# CE842170260_SHEET5.net
KiCad netlist of a schematic drawn in Altium Designer
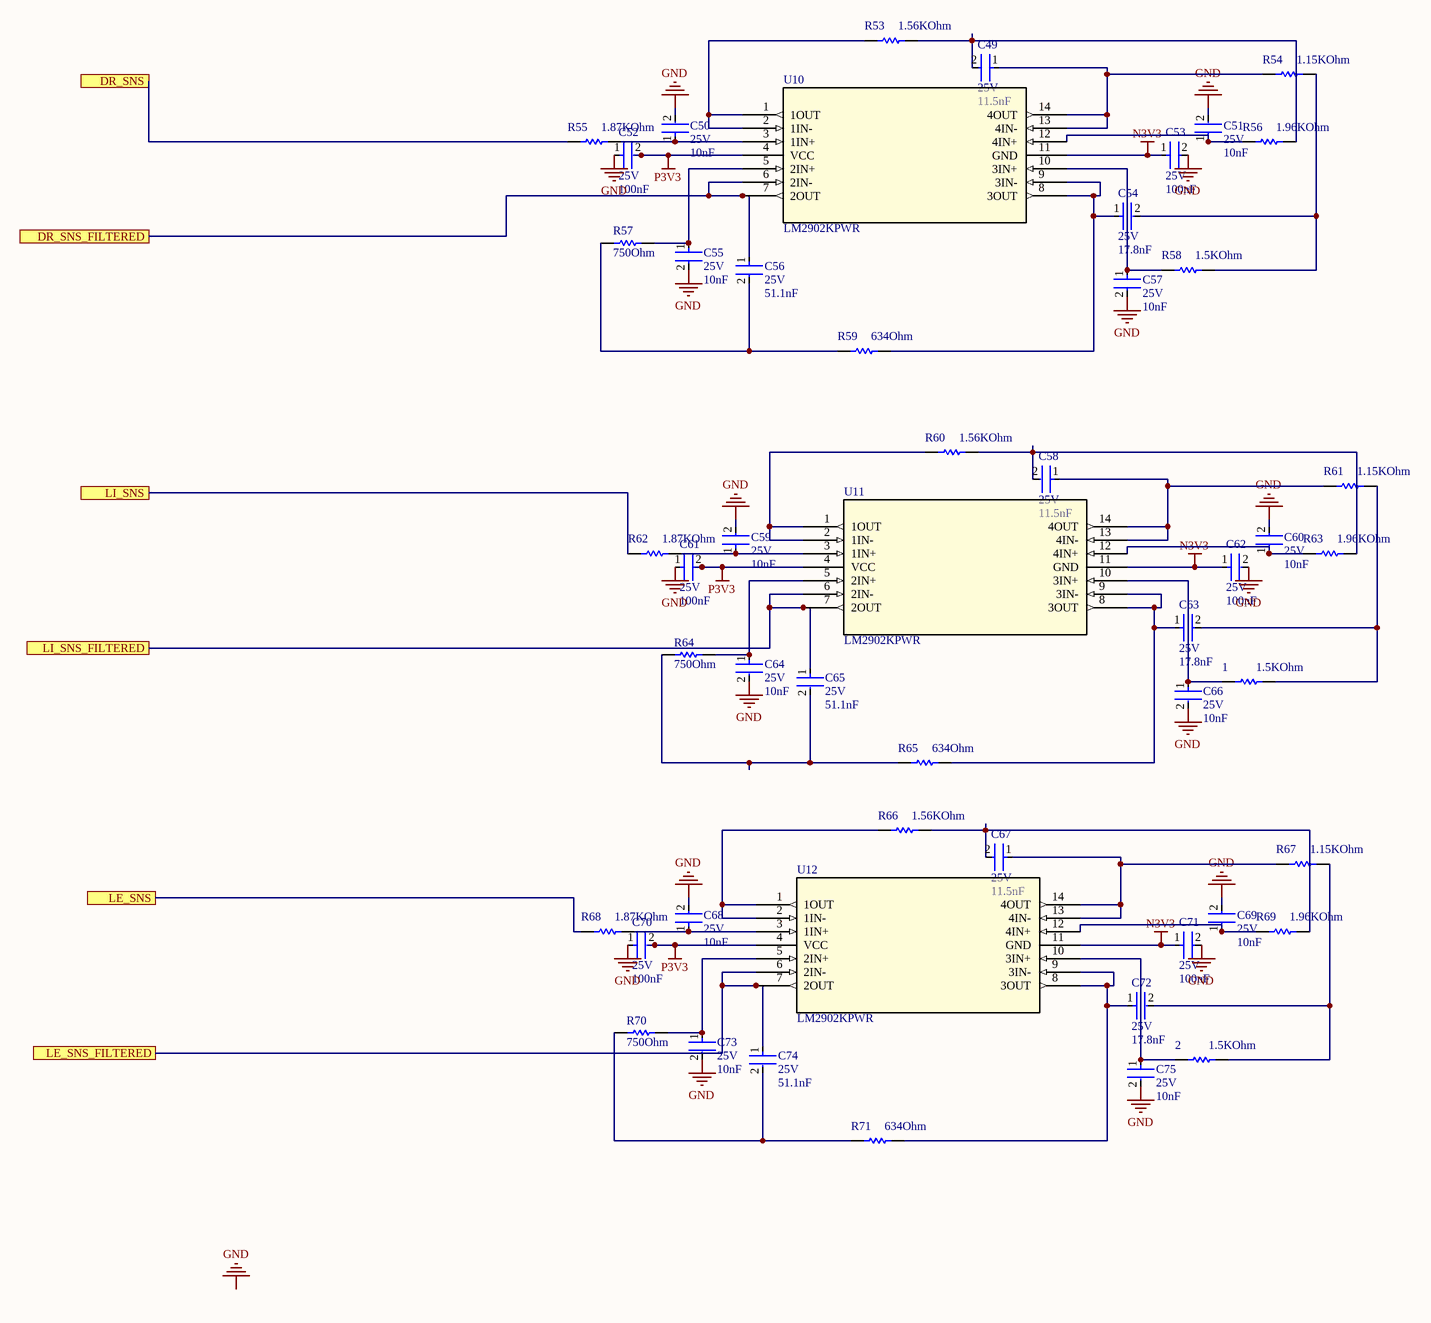
[diagram p0: CE842170260_SHEET5.SchDoc]

(export (version "E")
  (design (tool "Eeschema 10.0.6"))
  (components
    (comp (ref "1")
      (value "ERJ2RKF1002X")
      (footprint "RESC1005X40X25LL05T05")
      (description "Chip Resistor, 10 KOhm, +/- 1%, 0.1 W, -55 to 155 degC, 0402 (1005 Metric), RoHS, Tape and Reel")
      (fields
        (field (name "RESISTANCE") "1.5KOhm")
        (field (name "TOLERANCE") "1%")
        (field (name "MANUFACTURER") "Panasonic")
      )
      (libsource (lib "Altium Content Vault") (part "RES-2"))
    )
    (comp (ref "2")
      (value "ERJ2RKF1002X")
      (footprint "RESC1005X40X25LL05T05")
      (description "Chip Resistor, 10 KOhm, +/- 1%, 0.1 W, -55 to 155 degC, 0402 (1005 Metric), RoHS, Tape and Reel")
      (fields
        (field (name "RESISTANCE") "1.5KOhm")
        (field (name "TOLERANCE") "1%")
        (field (name "MANUFACTURER") "Panasonic")
      )
      (libsource (lib "Altium Content Vault") (part "RES-2"))
    )
    (comp (ref "C49")
      (value "C1005X5R1E104K050BC")
      (footprint "FP-C1005-050-0_05-MFG")
      (description "Multilayer Ceramic Capacitors 100nF ±10% 25V X5R SMD 0402")
      (fields
        (field (name "VOLTAGE RATING (DC)") "25V")
        (field (name "CAPACITANCE") "11.5nF")
        (field (name "TOLERANCE") "10%")
        (field (name "VOLTAGE") "25V")
      )
      (libsource (lib "Altium Content Vault") (part "b4654b650e69147ec39a6b967a45e02"))
    )
    (comp (ref "C50")
      (value "C1005X5R1E104K050BC")
      (footprint "FP-C1005-050-0_05-MFG")
      (description "Multilayer Ceramic Capacitors 100nF ±10% 25V X5R SMD 0402")
      (fields
        (field (name "VOLTAGE RATING (DC)") "25V")
        (field (name "CAPACITANCE") "10nF")
        (field (name "TOLERANCE") "10%")
        (field (name "VOLTAGE") "25V")
      )
      (libsource (lib "Altium Content Vault") (part "b4654b650e69147ec39a6b967a45e02"))
    )
    (comp (ref "C51")
      (value "C1005X5R1E104K050BC")
      (footprint "FP-C1005-050-0_05-MFG")
      (description "Multilayer Ceramic Capacitors 100nF ±10% 25V X5R SMD 0402")
      (fields
        (field (name "VOLTAGE RATING (DC)") "25V")
        (field (name "CAPACITANCE") "10nF")
        (field (name "TOLERANCE") "10%")
        (field (name "VOLTAGE") "25V")
      )
      (libsource (lib "Altium Content Vault") (part "b4654b650e69147ec39a6b967a45e02"))
    )
    (comp (ref "C52")
      (value "C1005X5R1E104K050BC")
      (footprint "FP-C1005-050-0_05-MFG")
      (description "Multilayer Ceramic Capacitors 100nF ±10% 25V X5R SMD 0402")
      (fields
        (field (name "VOLTAGE RATING (DC)") "25V")
        (field (name "CAPACITANCE") "100nF")
        (field (name "TOLERANCE") "10%")
        (field (name "VOLTAGE") "25V")
      )
      (libsource (lib "Altium Content Vault") (part "b4654b650e69147ec39a6b967a45e02"))
    )
    (comp (ref "C53")
      (value "C1005X5R1E104K050BC")
      (footprint "FP-C1005-050-0_05-MFG")
      (description "Multilayer Ceramic Capacitors 100nF ±10% 25V X5R SMD 0402")
      (fields
        (field (name "VOLTAGE RATING (DC)") "25V")
        (field (name "CAPACITANCE") "100nF")
        (field (name "TOLERANCE") "10%")
        (field (name "VOLTAGE") "25V")
      )
      (libsource (lib "Altium Content Vault") (part "b4654b650e69147ec39a6b967a45e02"))
    )
    (comp (ref "C54")
      (value "C1005X5R1E104K050BC")
      (footprint "FP-C1005-050-0_05-MFG")
      (description "Multilayer Ceramic Capacitors 100nF ±10% 25V X5R SMD 0402")
      (fields
        (field (name "VOLTAGE RATING (DC)") "25V")
        (field (name "CAPACITANCE") "17.8nF")
        (field (name "TOLERANCE") "10%")
        (field (name "VOLTAGE") "25V")
      )
      (libsource (lib "Altium Content Vault") (part "b4654b650e69147ec39a6b967a45e02"))
    )
    (comp (ref "C55")
      (value "C1005X5R1E104K050BC")
      (footprint "FP-C1005-050-0_05-MFG")
      (description "Multilayer Ceramic Capacitors 100nF ±10% 25V X5R SMD 0402")
      (fields
        (field (name "VOLTAGE RATING (DC)") "25V")
        (field (name "CAPACITANCE") "10nF")
        (field (name "TOLERANCE") "10%")
        (field (name "VOLTAGE") "25V")
      )
      (libsource (lib "Altium Content Vault") (part "b4654b650e69147ec39a6b967a45e02"))
    )
    (comp (ref "C56")
      (value "C1005X5R1E104K050BC")
      (footprint "FP-C1005-050-0_05-MFG")
      (description "Multilayer Ceramic Capacitors 100nF ±10% 25V X5R SMD 0402")
      (fields
        (field (name "VOLTAGE RATING (DC)") "25V")
        (field (name "CAPACITANCE") "51.1nF")
        (field (name "TOLERANCE") "10%")
        (field (name "VOLTAGE") "25V")
      )
      (libsource (lib "Altium Content Vault") (part "b4654b650e69147ec39a6b967a45e02"))
    )
    (comp (ref "C57")
      (value "C1005X5R1E104K050BC")
      (footprint "FP-C1005-050-0_05-MFG")
      (description "Multilayer Ceramic Capacitors 100nF ±10% 25V X5R SMD 0402")
      (fields
        (field (name "VOLTAGE RATING (DC)") "25V")
        (field (name "CAPACITANCE") "10nF")
        (field (name "TOLERANCE") "10%")
        (field (name "VOLTAGE") "25V")
      )
      (libsource (lib "Altium Content Vault") (part "b4654b650e69147ec39a6b967a45e02"))
    )
    (comp (ref "C58")
      (value "C1005X5R1E104K050BC")
      (footprint "FP-C1005-050-0_05-MFG")
      (description "Multilayer Ceramic Capacitors 100nF ±10% 25V X5R SMD 0402")
      (fields
        (field (name "VOLTAGE RATING (DC)") "25V")
        (field (name "CAPACITANCE") "11.5nF")
        (field (name "TOLERANCE") "10%")
        (field (name "VOLTAGE") "25V")
      )
      (libsource (lib "Altium Content Vault") (part "b4654b650e69147ec39a6b967a45e02"))
    )
    (comp (ref "C59")
      (value "C1005X5R1E104K050BC")
      (footprint "FP-C1005-050-0_05-MFG")
      (description "Multilayer Ceramic Capacitors 100nF ±10% 25V X5R SMD 0402")
      (fields
        (field (name "VOLTAGE RATING (DC)") "25V")
        (field (name "CAPACITANCE") "10nF")
        (field (name "TOLERANCE") "10%")
        (field (name "VOLTAGE") "25V")
      )
      (libsource (lib "Altium Content Vault") (part "b4654b650e69147ec39a6b967a45e02"))
    )
    (comp (ref "C60")
      (value "C1005X5R1E104K050BC")
      (footprint "FP-C1005-050-0_05-MFG")
      (description "Multilayer Ceramic Capacitors 100nF ±10% 25V X5R SMD 0402")
      (fields
        (field (name "VOLTAGE RATING (DC)") "25V")
        (field (name "CAPACITANCE") "10nF")
        (field (name "TOLERANCE") "10%")
        (field (name "VOLTAGE") "25V")
      )
      (libsource (lib "Altium Content Vault") (part "b4654b650e69147ec39a6b967a45e02"))
    )
    (comp (ref "C61")
      (value "C1005X5R1E104K050BC")
      (footprint "FP-C1005-050-0_05-MFG")
      (description "Multilayer Ceramic Capacitors 100nF ±10% 25V X5R SMD 0402")
      (fields
        (field (name "VOLTAGE RATING (DC)") "25V")
        (field (name "CAPACITANCE") "100nF")
        (field (name "TOLERANCE") "10%")
        (field (name "VOLTAGE") "25V")
      )
      (libsource (lib "Altium Content Vault") (part "b4654b650e69147ec39a6b967a45e02"))
    )
    (comp (ref "C62")
      (value "C1005X5R1E104K050BC")
      (footprint "FP-C1005-050-0_05-MFG")
      (description "Multilayer Ceramic Capacitors 100nF ±10% 25V X5R SMD 0402")
      (fields
        (field (name "VOLTAGE RATING (DC)") "25V")
        (field (name "CAPACITANCE") "100nF")
        (field (name "TOLERANCE") "10%")
        (field (name "VOLTAGE") "25V")
      )
      (libsource (lib "Altium Content Vault") (part "b4654b650e69147ec39a6b967a45e02"))
    )
    (comp (ref "C63")
      (value "C1005X5R1E104K050BC")
      (footprint "FP-C1005-050-0_05-MFG")
      (description "Multilayer Ceramic Capacitors 100nF ±10% 25V X5R SMD 0402")
      (fields
        (field (name "VOLTAGE RATING (DC)") "25V")
        (field (name "CAPACITANCE") "17.8nF")
        (field (name "TOLERANCE") "10%")
        (field (name "VOLTAGE") "25V")
      )
      (libsource (lib "Altium Content Vault") (part "b4654b650e69147ec39a6b967a45e02"))
    )
    (comp (ref "C64")
      (value "C1005X5R1E104K050BC")
      (footprint "FP-C1005-050-0_05-MFG")
      (description "Multilayer Ceramic Capacitors 100nF ±10% 25V X5R SMD 0402")
      (fields
        (field (name "VOLTAGE RATING (DC)") "25V")
        (field (name "CAPACITANCE") "10nF")
        (field (name "TOLERANCE") "10%")
        (field (name "VOLTAGE") "25V")
      )
      (libsource (lib "Altium Content Vault") (part "b4654b650e69147ec39a6b967a45e02"))
    )
    (comp (ref "C65")
      (value "C1005X5R1E104K050BC")
      (footprint "FP-C1005-050-0_05-MFG")
      (description "Multilayer Ceramic Capacitors 100nF ±10% 25V X5R SMD 0402")
      (fields
        (field (name "VOLTAGE RATING (DC)") "25V")
        (field (name "CAPACITANCE") "51.1nF")
        (field (name "TOLERANCE") "10%")
        (field (name "VOLTAGE") "25V")
      )
      (libsource (lib "Altium Content Vault") (part "b4654b650e69147ec39a6b967a45e02"))
    )
    (comp (ref "C66")
      (value "C1005X5R1E104K050BC")
      (footprint "FP-C1005-050-0_05-MFG")
      (description "Multilayer Ceramic Capacitors 100nF ±10% 25V X5R SMD 0402")
      (fields
        (field (name "VOLTAGE RATING (DC)") "25V")
        (field (name "CAPACITANCE") "10nF")
        (field (name "TOLERANCE") "10%")
        (field (name "VOLTAGE") "25V")
      )
      (libsource (lib "Altium Content Vault") (part "b4654b650e69147ec39a6b967a45e02"))
    )
    (comp (ref "C67")
      (value "C1005X5R1E104K050BC")
      (footprint "FP-C1005-050-0_05-MFG")
      (description "Multilayer Ceramic Capacitors 100nF ±10% 25V X5R SMD 0402")
      (fields
        (field (name "VOLTAGE RATING (DC)") "25V")
        (field (name "CAPACITANCE") "11.5nF")
        (field (name "TOLERANCE") "10%")
        (field (name "VOLTAGE") "25V")
      )
      (libsource (lib "Altium Content Vault") (part "b4654b650e69147ec39a6b967a45e02"))
    )
    (comp (ref "C68")
      (value "C1005X5R1E104K050BC")
      (footprint "FP-C1005-050-0_05-MFG")
      (description "Multilayer Ceramic Capacitors 100nF ±10% 25V X5R SMD 0402")
      (fields
        (field (name "VOLTAGE RATING (DC)") "25V")
        (field (name "CAPACITANCE") "10nF")
        (field (name "TOLERANCE") "10%")
        (field (name "VOLTAGE") "25V")
      )
      (libsource (lib "Altium Content Vault") (part "b4654b650e69147ec39a6b967a45e02"))
    )
    (comp (ref "C69")
      (value "C1005X5R1E104K050BC")
      (footprint "FP-C1005-050-0_05-MFG")
      (description "Multilayer Ceramic Capacitors 100nF ±10% 25V X5R SMD 0402")
      (fields
        (field (name "VOLTAGE RATING (DC)") "25V")
        (field (name "CAPACITANCE") "10nF")
        (field (name "TOLERANCE") "10%")
        (field (name "VOLTAGE") "25V")
      )
      (libsource (lib "Altium Content Vault") (part "b4654b650e69147ec39a6b967a45e02"))
    )
    (comp (ref "C70")
      (value "C1005X5R1E104K050BC")
      (footprint "FP-C1005-050-0_05-MFG")
      (description "Multilayer Ceramic Capacitors 100nF ±10% 25V X5R SMD 0402")
      (fields
        (field (name "VOLTAGE RATING (DC)") "25V")
        (field (name "CAPACITANCE") "100nF")
        (field (name "TOLERANCE") "10%")
        (field (name "VOLTAGE") "25V")
      )
      (libsource (lib "Altium Content Vault") (part "b4654b650e69147ec39a6b967a45e02"))
    )
    (comp (ref "C71")
      (value "C1005X5R1E104K050BC")
      (footprint "FP-C1005-050-0_05-MFG")
      (description "Multilayer Ceramic Capacitors 100nF ±10% 25V X5R SMD 0402")
      (fields
        (field (name "VOLTAGE RATING (DC)") "25V")
        (field (name "CAPACITANCE") "100nF")
        (field (name "TOLERANCE") "10%")
        (field (name "VOLTAGE") "25V")
      )
      (libsource (lib "Altium Content Vault") (part "b4654b650e69147ec39a6b967a45e02"))
    )
    (comp (ref "C72")
      (value "C1005X5R1E104K050BC")
      (footprint "FP-C1005-050-0_05-MFG")
      (description "Multilayer Ceramic Capacitors 100nF ±10% 25V X5R SMD 0402")
      (fields
        (field (name "VOLTAGE RATING (DC)") "25V")
        (field (name "CAPACITANCE") "17.8nF")
        (field (name "TOLERANCE") "10%")
        (field (name "VOLTAGE") "25V")
      )
      (libsource (lib "Altium Content Vault") (part "b4654b650e69147ec39a6b967a45e02"))
    )
    (comp (ref "C73")
      (value "C1005X5R1E104K050BC")
      (footprint "FP-C1005-050-0_05-MFG")
      (description "Multilayer Ceramic Capacitors 100nF ±10% 25V X5R SMD 0402")
      (fields
        (field (name "VOLTAGE RATING (DC)") "25V")
        (field (name "CAPACITANCE") "10nF")
        (field (name "TOLERANCE") "10%")
        (field (name "VOLTAGE") "25V")
      )
      (libsource (lib "Altium Content Vault") (part "b4654b650e69147ec39a6b967a45e02"))
    )
    (comp (ref "C74")
      (value "C1005X5R1E104K050BC")
      (footprint "FP-C1005-050-0_05-MFG")
      (description "Multilayer Ceramic Capacitors 100nF ±10% 25V X5R SMD 0402")
      (fields
        (field (name "VOLTAGE RATING (DC)") "25V")
        (field (name "CAPACITANCE") "51.1nF")
        (field (name "TOLERANCE") "10%")
        (field (name "VOLTAGE") "25V")
      )
      (libsource (lib "Altium Content Vault") (part "b4654b650e69147ec39a6b967a45e02"))
    )
    (comp (ref "C75")
      (value "C1005X5R1E104K050BC")
      (footprint "FP-C1005-050-0_05-MFG")
      (description "Multilayer Ceramic Capacitors 100nF ±10% 25V X5R SMD 0402")
      (fields
        (field (name "VOLTAGE RATING (DC)") "25V")
        (field (name "CAPACITANCE") "10nF")
        (field (name "TOLERANCE") "10%")
        (field (name "VOLTAGE") "25V")
      )
      (libsource (lib "Altium Content Vault") (part "b4654b650e69147ec39a6b967a45e02"))
    )
    (comp (ref "R53")
      (value "ERJ2RKF1002X")
      (footprint "RESC1005X40X25LL05T05")
      (description "Chip Resistor, 10 KOhm, +/- 1%, 0.1 W, -55 to 155 degC, 0402 (1005 Metric), RoHS, Tape and Reel")
      (fields
        (field (name "RESISTANCE") "1.56KOhm")
        (field (name "TOLERANCE") "1%")
        (field (name "MANUFACTURER") "Panasonic")
      )
      (libsource (lib "Altium Content Vault") (part "RES-2"))
    )
    (comp (ref "R54")
      (value "ERJ2RKF1002X")
      (footprint "RESC1005X40X25LL05T05")
      (description "Chip Resistor, 10 KOhm, +/- 1%, 0.1 W, -55 to 155 degC, 0402 (1005 Metric), RoHS, Tape and Reel")
      (fields
        (field (name "RESISTANCE") "1.15KOhm")
        (field (name "TOLERANCE") "1%")
        (field (name "MANUFACTURER") "Panasonic")
      )
      (libsource (lib "Altium Content Vault") (part "RES-2"))
    )
    (comp (ref "R55")
      (value "ERJ2RKF1002X")
      (footprint "RESC1005X40X25LL05T05")
      (description "Chip Resistor, 10 KOhm, +/- 1%, 0.1 W, -55 to 155 degC, 0402 (1005 Metric), RoHS, Tape and Reel")
      (fields
        (field (name "RESISTANCE") "1.87KOhm")
        (field (name "TOLERANCE") "1%")
        (field (name "MANUFACTURER") "Panasonic")
      )
      (libsource (lib "Altium Content Vault") (part "RES-2"))
    )
    (comp (ref "R56")
      (value "ERJ2RKF1002X")
      (footprint "RESC1005X40X25LL05T05")
      (description "Chip Resistor, 10 KOhm, +/- 1%, 0.1 W, -55 to 155 degC, 0402 (1005 Metric), RoHS, Tape and Reel")
      (fields
        (field (name "RESISTANCE") "1.96KOhm")
        (field (name "TOLERANCE") "1%")
        (field (name "MANUFACTURER") "Panasonic")
      )
      (libsource (lib "Altium Content Vault") (part "RES-2"))
    )
    (comp (ref "R57")
      (value "ERJ2RKF1002X")
      (footprint "RESC1005X40X25LL05T05")
      (description "Chip Resistor, 10 KOhm, +/- 1%, 0.1 W, -55 to 155 degC, 0402 (1005 Metric), RoHS, Tape and Reel")
      (fields
        (field (name "RESISTANCE") "750Ohm")
        (field (name "TOLERANCE") "1%")
        (field (name "MANUFACTURER") "Panasonic")
      )
      (libsource (lib "Altium Content Vault") (part "RES-2"))
    )
    (comp (ref "R58")
      (value "ERJ2RKF1002X")
      (footprint "RESC1005X40X25LL05T05")
      (description "Chip Resistor, 10 KOhm, +/- 1%, 0.1 W, -55 to 155 degC, 0402 (1005 Metric), RoHS, Tape and Reel")
      (fields
        (field (name "RESISTANCE") "1.5KOhm")
        (field (name "TOLERANCE") "1%")
        (field (name "MANUFACTURER") "Panasonic")
      )
      (libsource (lib "Altium Content Vault") (part "RES-2"))
    )
    (comp (ref "R59")
      (value "ERJ2RKF1002X")
      (footprint "RESC1005X40X25LL05T05")
      (description "Chip Resistor, 10 KOhm, +/- 1%, 0.1 W, -55 to 155 degC, 0402 (1005 Metric), RoHS, Tape and Reel")
      (fields
        (field (name "RESISTANCE") "634Ohm")
        (field (name "TOLERANCE") "1%")
        (field (name "MANUFACTURER") "Panasonic")
      )
      (libsource (lib "Altium Content Vault") (part "RES-2"))
    )
    (comp (ref "R60")
      (value "ERJ2RKF1002X")
      (footprint "RESC1005X40X25LL05T05")
      (description "Chip Resistor, 10 KOhm, +/- 1%, 0.1 W, -55 to 155 degC, 0402 (1005 Metric), RoHS, Tape and Reel")
      (fields
        (field (name "RESISTANCE") "1.56KOhm")
        (field (name "TOLERANCE") "1%")
        (field (name "MANUFACTURER") "Panasonic")
      )
      (libsource (lib "Altium Content Vault") (part "RES-2"))
    )
    (comp (ref "R61")
      (value "ERJ2RKF1002X")
      (footprint "RESC1005X40X25LL05T05")
      (description "Chip Resistor, 10 KOhm, +/- 1%, 0.1 W, -55 to 155 degC, 0402 (1005 Metric), RoHS, Tape and Reel")
      (fields
        (field (name "RESISTANCE") "1.15KOhm")
        (field (name "TOLERANCE") "1%")
        (field (name "MANUFACTURER") "Panasonic")
      )
      (libsource (lib "Altium Content Vault") (part "RES-2"))
    )
    (comp (ref "R62")
      (value "ERJ2RKF1002X")
      (footprint "RESC1005X40X25LL05T05")
      (description "Chip Resistor, 10 KOhm, +/- 1%, 0.1 W, -55 to 155 degC, 0402 (1005 Metric), RoHS, Tape and Reel")
      (fields
        (field (name "RESISTANCE") "1.87KOhm")
        (field (name "TOLERANCE") "1%")
        (field (name "MANUFACTURER") "Panasonic")
      )
      (libsource (lib "Altium Content Vault") (part "RES-2"))
    )
    (comp (ref "R63")
      (value "ERJ2RKF1002X")
      (footprint "RESC1005X40X25LL05T05")
      (description "Chip Resistor, 10 KOhm, +/- 1%, 0.1 W, -55 to 155 degC, 0402 (1005 Metric), RoHS, Tape and Reel")
      (fields
        (field (name "RESISTANCE") "1.96KOhm")
        (field (name "TOLERANCE") "1%")
        (field (name "MANUFACTURER") "Panasonic")
      )
      (libsource (lib "Altium Content Vault") (part "RES-2"))
    )
    (comp (ref "R64")
      (value "ERJ2RKF1002X")
      (footprint "RESC1005X40X25LL05T05")
      (description "Chip Resistor, 10 KOhm, +/- 1%, 0.1 W, -55 to 155 degC, 0402 (1005 Metric), RoHS, Tape and Reel")
      (fields
        (field (name "RESISTANCE") "750Ohm")
        (field (name "TOLERANCE") "1%")
        (field (name "MANUFACTURER") "Panasonic")
      )
      (libsource (lib "Altium Content Vault") (part "RES-2"))
    )
    (comp (ref "R65")
      (value "ERJ2RKF1002X")
      (footprint "RESC1005X40X25LL05T05")
      (description "Chip Resistor, 10 KOhm, +/- 1%, 0.1 W, -55 to 155 degC, 0402 (1005 Metric), RoHS, Tape and Reel")
      (fields
        (field (name "RESISTANCE") "634Ohm")
        (field (name "TOLERANCE") "1%")
        (field (name "MANUFACTURER") "Panasonic")
      )
      (libsource (lib "Altium Content Vault") (part "RES-2"))
    )
    (comp (ref "R66")
      (value "ERJ2RKF1002X")
      (footprint "RESC1005X40X25LL05T05")
      (description "Chip Resistor, 10 KOhm, +/- 1%, 0.1 W, -55 to 155 degC, 0402 (1005 Metric), RoHS, Tape and Reel")
      (fields
        (field (name "RESISTANCE") "1.56KOhm")
        (field (name "TOLERANCE") "1%")
        (field (name "MANUFACTURER") "Panasonic")
      )
      (libsource (lib "Altium Content Vault") (part "RES-2"))
    )
    (comp (ref "R67")
      (value "ERJ2RKF1002X")
      (footprint "RESC1005X40X25LL05T05")
      (description "Chip Resistor, 10 KOhm, +/- 1%, 0.1 W, -55 to 155 degC, 0402 (1005 Metric), RoHS, Tape and Reel")
      (fields
        (field (name "RESISTANCE") "1.15KOhm")
        (field (name "TOLERANCE") "1%")
        (field (name "MANUFACTURER") "Panasonic")
      )
      (libsource (lib "Altium Content Vault") (part "RES-2"))
    )
    (comp (ref "R68")
      (value "ERJ2RKF1002X")
      (footprint "RESC1005X40X25LL05T05")
      (description "Chip Resistor, 10 KOhm, +/- 1%, 0.1 W, -55 to 155 degC, 0402 (1005 Metric), RoHS, Tape and Reel")
      (fields
        (field (name "RESISTANCE") "1.87KOhm")
        (field (name "TOLERANCE") "1%")
        (field (name "MANUFACTURER") "Panasonic")
      )
      (libsource (lib "Altium Content Vault") (part "RES-2"))
    )
    (comp (ref "R69")
      (value "ERJ2RKF1002X")
      (footprint "RESC1005X40X25LL05T05")
      (description "Chip Resistor, 10 KOhm, +/- 1%, 0.1 W, -55 to 155 degC, 0402 (1005 Metric), RoHS, Tape and Reel")
      (fields
        (field (name "RESISTANCE") "1.96KOhm")
        (field (name "TOLERANCE") "1%")
        (field (name "MANUFACTURER") "Panasonic")
      )
      (libsource (lib "Altium Content Vault") (part "RES-2"))
    )
    (comp (ref "R70")
      (value "ERJ2RKF1002X")
      (footprint "RESC1005X40X25LL05T05")
      (description "Chip Resistor, 10 KOhm, +/- 1%, 0.1 W, -55 to 155 degC, 0402 (1005 Metric), RoHS, Tape and Reel")
      (fields
        (field (name "RESISTANCE") "750Ohm")
        (field (name "TOLERANCE") "1%")
        (field (name "MANUFACTURER") "Panasonic")
      )
      (libsource (lib "Altium Content Vault") (part "RES-2"))
    )
    (comp (ref "R71")
      (value "ERJ2RKF1002X")
      (footprint "RESC1005X40X25LL05T05")
      (description "Chip Resistor, 10 KOhm, +/- 1%, 0.1 W, -55 to 155 degC, 0402 (1005 Metric), RoHS, Tape and Reel")
      (fields
        (field (name "RESISTANCE") "634Ohm")
        (field (name "TOLERANCE") "1%")
        (field (name "MANUFACTURER") "Panasonic")
      )
      (libsource (lib "Altium Content Vault") (part "RES-2"))
    )
    (comp (ref "U10")
      (value "LM2902KPWR")
      (footprint "PW14")
      (description "No Description Available")
      (fields (field (name "COPYRIGHT") "Copyright (C) 2023 Ultra Librarian. All rights reserved."))
      (libsource (lib "LM2902KPWR") (part "LM2902KPWR"))
    )
    (comp (ref "U11")
      (value "LM2902KPWR")
      (footprint "PW14")
      (description "No Description Available")
      (fields (field (name "COPYRIGHT") "Copyright (C) 2023 Ultra Librarian. All rights reserved."))
      (libsource (lib "LM2902KPWR") (part "LM2902KPWR"))
    )
    (comp (ref "U12")
      (value "LM2902KPWR")
      (footprint "PW14")
      (description "No Description Available")
      (fields (field (name "COPYRIGHT") "Copyright (C) 2023 Ultra Librarian. All rights reserved."))
      (libsource (lib "LM2902KPWR") (part "LM2902KPWR"))
    )
  )
  (nets
    (net (code "1") (name "/DR_SNS") (class "Default")
      (node (ref "R55") (pin "1") (pinfunction "1_1") (pintype "passive"))
    )
    (net (code "2") (name "/DR_SNS_FILTERED") (class "Default")
      (node (ref "C56") (pin "1") (pinfunction "1_1") (pintype "passive"))
      (node (ref "U10") (pin "6") (pinfunction "2IN-_6") (pintype "input"))
      (node (ref "U10") (pin "7") (pinfunction "2OUT_7") (pintype "output"))
    )
    (net (code "3") (name "/LE_SNS") (class "Default")
      (node (ref "R68") (pin "1") (pinfunction "1_1") (pintype "passive"))
    )
    (net (code "4") (name "/LE_SNS_FILTERED") (class "Default")
      (node (ref "C74") (pin "1") (pinfunction "1_1") (pintype "passive"))
      (node (ref "U12") (pin "6") (pinfunction "2IN-_6") (pintype "input"))
      (node (ref "U12") (pin "7") (pinfunction "2OUT_7") (pintype "output"))
    )
    (net (code "5") (name "/LI_SNS") (class "Default")
      (node (ref "R62") (pin "1") (pinfunction "1_1") (pintype "passive"))
    )
    (net (code "6") (name "/LI_SNS_FILTERED") (class "Default")
      (node (ref "C65") (pin "1") (pinfunction "1_1") (pintype "passive"))
      (node (ref "U11") (pin "6") (pinfunction "2IN-_6") (pintype "input"))
      (node (ref "U11") (pin "7") (pinfunction "2OUT_7") (pintype "output"))
    )
    (net (code "7") (name "GND") (class "Default")
      (node (ref "C50") (pin "2") (pinfunction "2_2") (pintype "passive"))
      (node (ref "C51") (pin "2") (pinfunction "2_2") (pintype "passive"))
      (node (ref "C52") (pin "1") (pinfunction "1_1") (pintype "passive"))
      (node (ref "C53") (pin "2") (pinfunction "2_2") (pintype "passive"))
      (node (ref "C55") (pin "2") (pinfunction "2_2") (pintype "passive"))
      (node (ref "C57") (pin "2") (pinfunction "2_2") (pintype "passive"))
      (node (ref "C59") (pin "2") (pinfunction "2_2") (pintype "passive"))
      (node (ref "C60") (pin "2") (pinfunction "2_2") (pintype "passive"))
      (node (ref "C61") (pin "1") (pinfunction "1_1") (pintype "passive"))
      (node (ref "C62") (pin "2") (pinfunction "2_2") (pintype "passive"))
      (node (ref "C64") (pin "2") (pinfunction "2_2") (pintype "passive"))
      (node (ref "C66") (pin "2") (pinfunction "2_2") (pintype "passive"))
      (node (ref "C68") (pin "2") (pinfunction "2_2") (pintype "passive"))
      (node (ref "C69") (pin "2") (pinfunction "2_2") (pintype "passive"))
      (node (ref "C70") (pin "1") (pinfunction "1_1") (pintype "passive"))
      (node (ref "C71") (pin "2") (pinfunction "2_2") (pintype "passive"))
      (node (ref "C73") (pin "2") (pinfunction "2_2") (pintype "passive"))
      (node (ref "C75") (pin "2") (pinfunction "2_2") (pintype "passive"))
    )
    (net (code "8") (name "N3V3") (class "Default")
      (node (ref "C53") (pin "1") (pinfunction "1_1") (pintype "passive"))
      (node (ref "C62") (pin "1") (pinfunction "1_1") (pintype "passive"))
      (node (ref "C71") (pin "1") (pinfunction "1_1") (pintype "passive"))
      (node (ref "U10") (pin "11") (pinfunction "GND_11") (pintype "power_in"))
      (node (ref "U11") (pin "11") (pinfunction "GND_11") (pintype "power_in"))
      (node (ref "U12") (pin "11") (pinfunction "GND_11") (pintype "power_in"))
    )
    (net (code "9") (name "Net-(1-Pad2)") (class "Default")
      (node (ref "1") (pin "2") (pinfunction "2_2") (pintype "passive"))
      (node (ref "C63") (pin "2") (pinfunction "2_2") (pintype "passive"))
      (node (ref "R61") (pin "2") (pinfunction "2_2") (pintype "passive"))
    )
    (net (code "10") (name "Net-(2-Pad2)") (class "Default")
      (node (ref "2") (pin "2") (pinfunction "2_2") (pintype "passive"))
      (node (ref "C72") (pin "2") (pinfunction "2_2") (pintype "passive"))
      (node (ref "R67") (pin "2") (pinfunction "2_2") (pintype "passive"))
    )
    (net (code "11") (name "Net-(C49-Pad2)") (class "Default")
      (node (ref "C49") (pin "2") (pinfunction "2_2") (pintype "passive"))
      (node (ref "R53") (pin "2") (pinfunction "2_2") (pintype "passive"))
      (node (ref "R56") (pin "2") (pinfunction "2_2") (pintype "passive"))
    )
    (net (code "12") (name "Net-(C54-Pad2)") (class "Default")
      (node (ref "C54") (pin "2") (pinfunction "2_2") (pintype "passive"))
      (node (ref "R54") (pin "2") (pinfunction "2_2") (pintype "passive"))
      (node (ref "R58") (pin "2") (pinfunction "2_2") (pintype "passive"))
    )
    (net (code "13") (name "Net-(C56-Pad2)") (class "Default")
      (node (ref "C56") (pin "2") (pinfunction "2_2") (pintype "passive"))
      (node (ref "R57") (pin "2") (pinfunction "2_2") (pintype "passive"))
      (node (ref "R59") (pin "1") (pinfunction "1_1") (pintype "passive"))
    )
    (net (code "14") (name "Net-(C58-Pad2)") (class "Default")
      (node (ref "C58") (pin "2") (pinfunction "2_2") (pintype "passive"))
      (node (ref "R60") (pin "2") (pinfunction "2_2") (pintype "passive"))
      (node (ref "R63") (pin "2") (pinfunction "2_2") (pintype "passive"))
    )
    (net (code "15") (name "Net-(C65-Pad2)") (class "Default")
      (node (ref "C65") (pin "2") (pinfunction "2_2") (pintype "passive"))
      (node (ref "R64") (pin "2") (pinfunction "2_2") (pintype "passive"))
      (node (ref "R65") (pin "1") (pinfunction "1_1") (pintype "passive"))
    )
    (net (code "16") (name "Net-(C67-Pad2)") (class "Default")
      (node (ref "C67") (pin "2") (pinfunction "2_2") (pintype "passive"))
      (node (ref "R66") (pin "2") (pinfunction "2_2") (pintype "passive"))
      (node (ref "R69") (pin "2") (pinfunction "2_2") (pintype "passive"))
    )
    (net (code "17") (name "Net-(C74-Pad2)") (class "Default")
      (node (ref "C74") (pin "2") (pinfunction "2_2") (pintype "passive"))
      (node (ref "R70") (pin "2") (pinfunction "2_2") (pintype "passive"))
      (node (ref "R71") (pin "1") (pinfunction "1_1") (pintype "passive"))
    )
    (net (code "18") (name "Net-(U10-1IN+)") (class "Default")
      (node (ref "C50") (pin "1") (pinfunction "1_1") (pintype "passive"))
      (node (ref "R55") (pin "2") (pinfunction "2_2") (pintype "passive"))
      (node (ref "U10") (pin "3") (pinfunction "1IN+_3") (pintype "input"))
    )
    (net (code "19") (name "Net-(U10-1IN-)") (class "Default")
      (node (ref "R53") (pin "1") (pinfunction "1_1") (pintype "passive"))
      (node (ref "U10") (pin "1") (pinfunction "1OUT_1") (pintype "output"))
      (node (ref "U10") (pin "2") (pinfunction "1IN-_2") (pintype "input"))
    )
    (net (code "20") (name "Net-(U10-2IN+)") (class "Default")
      (node (ref "C55") (pin "1") (pinfunction "1_1") (pintype "passive"))
      (node (ref "R57") (pin "1") (pinfunction "1_1") (pintype "passive"))
      (node (ref "U10") (pin "5") (pinfunction "2IN+_5") (pintype "input"))
    )
    (net (code "21") (name "Net-(U10-3IN+)") (class "Default")
      (node (ref "C57") (pin "1") (pinfunction "1_1") (pintype "passive"))
      (node (ref "R58") (pin "1") (pinfunction "1_1") (pintype "passive"))
      (node (ref "U10") (pin "10") (pinfunction "3IN+_10") (pintype "input"))
    )
    (net (code "22") (name "Net-(U10-3IN-)") (class "Default")
      (node (ref "C54") (pin "1") (pinfunction "1_1") (pintype "passive"))
      (node (ref "R59") (pin "2") (pinfunction "2_2") (pintype "passive"))
      (node (ref "U10") (pin "8") (pinfunction "3OUT_8") (pintype "output"))
      (node (ref "U10") (pin "9") (pinfunction "3IN-_9") (pintype "input"))
    )
    (net (code "23") (name "Net-(U10-4IN+)") (class "Default")
      (node (ref "C51") (pin "1") (pinfunction "1_1") (pintype "passive"))
      (node (ref "R56") (pin "1") (pinfunction "1_1") (pintype "passive"))
      (node (ref "U10") (pin "12") (pinfunction "4IN+_12") (pintype "input"))
    )
    (net (code "24") (name "Net-(U10-4IN-)") (class "Default")
      (node (ref "C49") (pin "1") (pinfunction "1_1") (pintype "passive"))
      (node (ref "R54") (pin "1") (pinfunction "1_1") (pintype "passive"))
      (node (ref "U10") (pin "13") (pinfunction "4IN-_13") (pintype "input"))
      (node (ref "U10") (pin "14") (pinfunction "4OUT_14") (pintype "output"))
    )
    (net (code "25") (name "Net-(U11-1IN+)") (class "Default")
      (node (ref "C59") (pin "1") (pinfunction "1_1") (pintype "passive"))
      (node (ref "R62") (pin "2") (pinfunction "2_2") (pintype "passive"))
      (node (ref "U11") (pin "3") (pinfunction "1IN+_3") (pintype "input"))
    )
    (net (code "26") (name "Net-(U11-1IN-)") (class "Default")
      (node (ref "R60") (pin "1") (pinfunction "1_1") (pintype "passive"))
      (node (ref "U11") (pin "1") (pinfunction "1OUT_1") (pintype "output"))
      (node (ref "U11") (pin "2") (pinfunction "1IN-_2") (pintype "input"))
    )
    (net (code "27") (name "Net-(U11-2IN+)") (class "Default")
      (node (ref "C64") (pin "1") (pinfunction "1_1") (pintype "passive"))
      (node (ref "R64") (pin "1") (pinfunction "1_1") (pintype "passive"))
      (node (ref "U11") (pin "5") (pinfunction "2IN+_5") (pintype "input"))
    )
    (net (code "28") (name "Net-(U11-3IN+)") (class "Default")
      (node (ref "1") (pin "1") (pinfunction "1_1") (pintype "passive"))
      (node (ref "C66") (pin "1") (pinfunction "1_1") (pintype "passive"))
      (node (ref "U11") (pin "10") (pinfunction "3IN+_10") (pintype "input"))
    )
    (net (code "29") (name "Net-(U11-3IN-)") (class "Default")
      (node (ref "C63") (pin "1") (pinfunction "1_1") (pintype "passive"))
      (node (ref "R65") (pin "2") (pinfunction "2_2") (pintype "passive"))
      (node (ref "U11") (pin "8") (pinfunction "3OUT_8") (pintype "output"))
      (node (ref "U11") (pin "9") (pinfunction "3IN-_9") (pintype "input"))
    )
    (net (code "30") (name "Net-(U11-4IN+)") (class "Default")
      (node (ref "C60") (pin "1") (pinfunction "1_1") (pintype "passive"))
      (node (ref "R63") (pin "1") (pinfunction "1_1") (pintype "passive"))
      (node (ref "U11") (pin "12") (pinfunction "4IN+_12") (pintype "input"))
    )
    (net (code "31") (name "Net-(U11-4IN-)") (class "Default")
      (node (ref "C58") (pin "1") (pinfunction "1_1") (pintype "passive"))
      (node (ref "R61") (pin "1") (pinfunction "1_1") (pintype "passive"))
      (node (ref "U11") (pin "13") (pinfunction "4IN-_13") (pintype "input"))
      (node (ref "U11") (pin "14") (pinfunction "4OUT_14") (pintype "output"))
    )
    (net (code "32") (name "Net-(U12-1IN+)") (class "Default")
      (node (ref "C68") (pin "1") (pinfunction "1_1") (pintype "passive"))
      (node (ref "R68") (pin "2") (pinfunction "2_2") (pintype "passive"))
      (node (ref "U12") (pin "3") (pinfunction "1IN+_3") (pintype "input"))
    )
    (net (code "33") (name "Net-(U12-1IN-)") (class "Default")
      (node (ref "R66") (pin "1") (pinfunction "1_1") (pintype "passive"))
      (node (ref "U12") (pin "1") (pinfunction "1OUT_1") (pintype "output"))
      (node (ref "U12") (pin "2") (pinfunction "1IN-_2") (pintype "input"))
    )
    (net (code "34") (name "Net-(U12-2IN+)") (class "Default")
      (node (ref "C73") (pin "1") (pinfunction "1_1") (pintype "passive"))
      (node (ref "R70") (pin "1") (pinfunction "1_1") (pintype "passive"))
      (node (ref "U12") (pin "5") (pinfunction "2IN+_5") (pintype "input"))
    )
    (net (code "35") (name "Net-(U12-3IN+)") (class "Default")
      (node (ref "2") (pin "1") (pinfunction "1_1") (pintype "passive"))
      (node (ref "C75") (pin "1") (pinfunction "1_1") (pintype "passive"))
      (node (ref "U12") (pin "10") (pinfunction "3IN+_10") (pintype "input"))
    )
    (net (code "36") (name "Net-(U12-3IN-)") (class "Default")
      (node (ref "C72") (pin "1") (pinfunction "1_1") (pintype "passive"))
      (node (ref "R71") (pin "2") (pinfunction "2_2") (pintype "passive"))
      (node (ref "U12") (pin "8") (pinfunction "3OUT_8") (pintype "output"))
      (node (ref "U12") (pin "9") (pinfunction "3IN-_9") (pintype "input"))
    )
    (net (code "37") (name "Net-(U12-4IN+)") (class "Default")
      (node (ref "C69") (pin "1") (pinfunction "1_1") (pintype "passive"))
      (node (ref "R69") (pin "1") (pinfunction "1_1") (pintype "passive"))
      (node (ref "U12") (pin "12") (pinfunction "4IN+_12") (pintype "input"))
    )
    (net (code "38") (name "Net-(U12-4IN-)") (class "Default")
      (node (ref "C67") (pin "1") (pinfunction "1_1") (pintype "passive"))
      (node (ref "R67") (pin "1") (pinfunction "1_1") (pintype "passive"))
      (node (ref "U12") (pin "13") (pinfunction "4IN-_13") (pintype "input"))
      (node (ref "U12") (pin "14") (pinfunction "4OUT_14") (pintype "output"))
    )
    (net (code "39") (name "P3V3") (class "Default")
      (node (ref "C52") (pin "2") (pinfunction "2_2") (pintype "passive"))
      (node (ref "C61") (pin "2") (pinfunction "2_2") (pintype "passive"))
      (node (ref "C70") (pin "2") (pinfunction "2_2") (pintype "passive"))
      (node (ref "U10") (pin "4") (pinfunction "VCC_4") (pintype "power_in"))
      (node (ref "U11") (pin "4") (pinfunction "VCC_4") (pintype "power_in"))
      (node (ref "U12") (pin "4") (pinfunction "VCC_4") (pintype "power_in"))
    )
  )
)
